# triac.net
KiCad netlist of a schematic drawn in Altium Designer
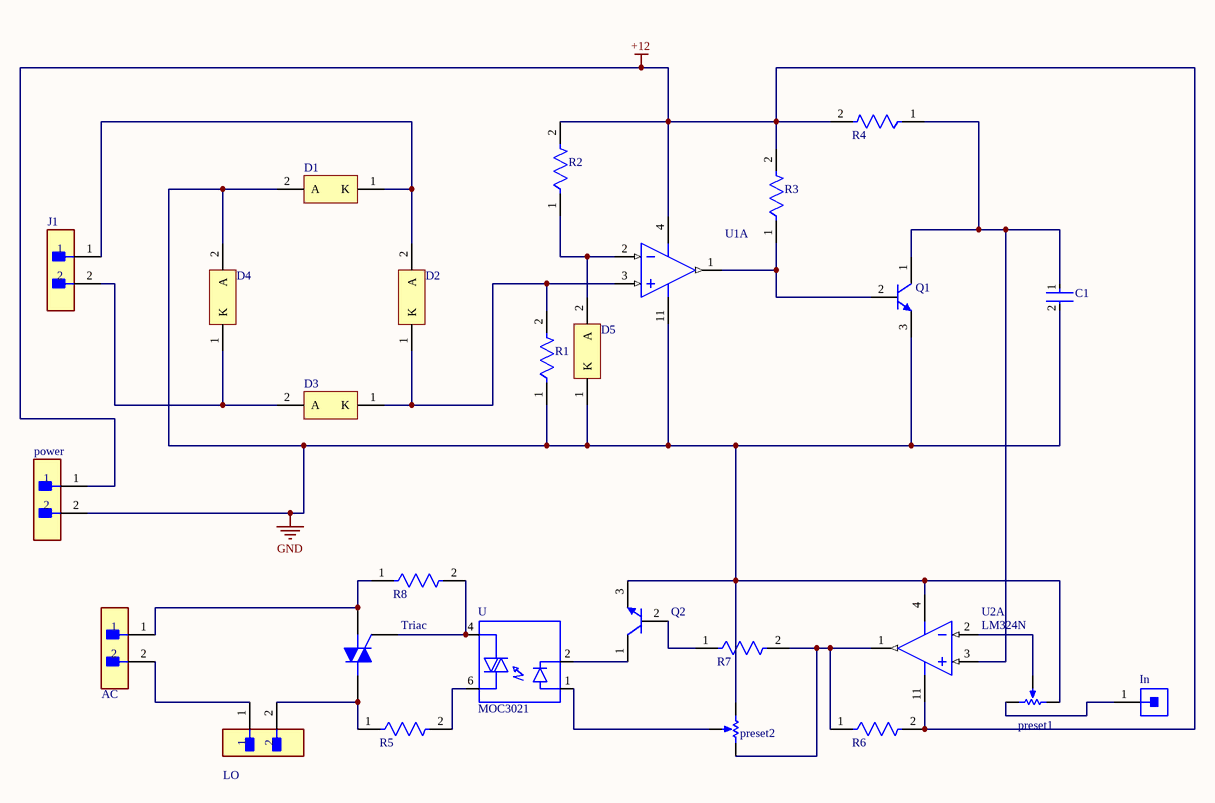
[diagram p0: triac.SchDoc]

(export (version "E")
  (design (tool "Eeschema 10.0.6"))
  (components
    (comp (ref "AC")
      (value "M20-9990246")
      (footprint "FP-M20-9990246-MFG")
      (description "CONN HEADER VERT 2POS 2.54MM")
      (fields
        (field (name "OCTOPART") "https://octopart.com/m20-9990246-harwin-2590635")
        (field (name "MANUFACTURER") "Harwin")
      )
      (libsource (lib "Altium Content Vault") (part "3bc925449376181038e59eaffc5286c"))
    )
    (comp (ref "C1")
      (value "RCE5C1H332J0M1H03A")
      (footprint "FP-RCE0K1-MFG")
      (description "Cap Ceramic 3.3nF 50V C0G ±5% Radial 5mm +125°C Automotive Bulk")
      (fields (field (name "TOLERANCE") "5%"))
      (libsource (lib "Altium Content Vault") (part "b4654b650e69147ec39a6b967a45e02"))
    )
    (comp (ref "D1")
      (value "1N4007G")
      (footprint "ONSC-AXIAL_LEAD-2-59-10_P")
      (description "Standard Recovery Rectifier, 2-Pin Axial_Lead, Pb-Free, Bulk Bag")
      (fields (field (name "MANUFACTURER") "On Semiconductor"))
      (libsource (lib "") (part "ONSC-D-K1A2-2_A_1"))
    )
    (comp (ref "D2")
      (value "1N4007G")
      (footprint "ONSC-AXIAL_LEAD-2-59-10_P")
      (description "Standard Recovery Rectifier, 2-Pin Axial_Lead, Pb-Free, Bulk Bag")
      (fields (field (name "MANUFACTURER") "On Semiconductor"))
      (libsource (lib "Altium Content Vault") (part "ONSC-D-K1A2-2_A"))
    )
    (comp (ref "D3")
      (value "1N4007G")
      (footprint "ONSC-AXIAL_LEAD-2-59-10_P")
      (description "Standard Recovery Rectifier, 2-Pin Axial_Lead, Pb-Free, Bulk Bag")
      (fields (field (name "MANUFACTURER") "On Semiconductor"))
      (libsource (lib "") (part "ONSC-D-K1A2-2_A_1"))
    )
    (comp (ref "D4")
      (value "1N4007G")
      (footprint "ONSC-AXIAL_LEAD-2-59-10_P")
      (description "Standard Recovery Rectifier, 2-Pin Axial_Lead, Pb-Free, Bulk Bag")
      (fields (field (name "MANUFACTURER") "On Semiconductor"))
      (libsource (lib "Altium Content Vault") (part "ONSC-D-K1A2-2_A"))
    )
    (comp (ref "D5")
      (value "1N4007G")
      (footprint "ONSC-AXIAL_LEAD-2-59-10_P")
      (description "Standard Recovery Rectifier, 2-Pin Axial_Lead, Pb-Free, Bulk Bag")
      (fields (field (name "MANUFACTURER") "On Semiconductor"))
      (libsource (lib "Altium Content Vault") (part "ONSC-D-K1A2-2_A"))
    )
    (comp (ref "In")
      (value "61300111121")
      (footprint "61300111121")
      (description "THT Vertical Pin Header WR-PHD, Pitch 2.54 mm, Single Row, 1 pins")
      (fields (field (name "MANUFACTURER") "Wurth Elektronik") (field (name "PUBLISHER") "WurthElektronik"))
      (libsource (lib "Altium Content Vault") (part "WE-CN-1P-M-R1"))
    )
    (comp (ref "J1")
      (value "M20-9990246")
      (footprint "FP-M20-9990246-MFG")
      (description "CONN HEADER VERT 2POS 2.54MM")
      (fields
        (field (name "OCTOPART") "https://octopart.com/m20-9990246-harwin-2590635")
        (field (name "MANUFACTURER") "Harwin")
      )
      (libsource (lib "Altium Content Vault") (part "3bc925449376181038e59eaffc5286c"))
    )
    (comp (ref "LO")
      (value "M20-9990246")
      (footprint "FP-M20-9990246-MFG")
      (description "CONN HEADER VERT 2POS 2.54MM")
      (fields
        (field (name "OCTOPART") "https://octopart.com/m20-9990246-harwin-2590635")
        (field (name "MANUFACTURER") "Harwin")
      )
      (libsource (lib "") (part "3bc925449376181038e59eaffc5286c_1"))
    )
    (comp (ref "power")
      (value "M20-9990246")
      (footprint "FP-M20-9990246-MFG")
      (description "CONN HEADER VERT 2POS 2.54MM")
      (fields
        (field (name "OCTOPART") "https://octopart.com/m20-9990246-harwin-2590635")
        (field (name "MANUFACTURER") "Harwin")
      )
      (libsource (lib "Altium Content Vault") (part "3bc925449376181038e59eaffc5286c"))
    )
    (comp (ref "preset1")
      (value "3362P-1-103LF")
      (footprint "BOUR-3362P")
      (description "Square Trimpot(R) Trimming Potentiometer, 10 KOhm, 300 V, -55 to 125 degC, 3-Pin THD, RoHS, Tube")
      (fields (field (name "TOLERANCE") "1%"))
      (libsource (lib "Altium Content Vault") (part "RES-POT-3"))
    )
    (comp (ref "preset2")
      (value "3362P-1-103LF")
      (footprint "BOUR-3362P")
      (description "Square Trimpot(R) Trimming Potentiometer, 10 KOhm, 300 V, -55 to 125 degC, 3-Pin THD, RoHS, Tube")
      (fields (field (name "TOLERANCE") "1%"))
      (libsource (lib "Altium Content Vault") (part "RES-POT-3"))
    )
    (comp (ref "Q1")
      (value "BC547BG")
      (footprint "ONSC-TO-92-3-29-11")
      (description "Amplifier Transistor, NPN Silicon, 3-Pin TO-92, Pb-Free, Bulk Box")
      (fields (field (name "MANUFACTURER") "On Semiconductor"))
      (libsource (lib "Altium Content Vault") (part "ONSC-NPN-C1B2E3-3"))
    )
    (comp (ref "Q2")
      (value "BC547BG")
      (footprint "ONSC-TO-92-3-29-11")
      (description "Amplifier Transistor, NPN Silicon, 3-Pin TO-92, Pb-Free, Bulk Box")
      (fields (field (name "MANUFACTURER") "On Semiconductor"))
      (libsource (lib "Altium Content Vault") (part "ONSC-NPN-C1B2E3-3"))
    )
    (comp (ref "R1")
      (value "MFR-25FBF52-1K18")
      (footprint "FP-MFR-25-MFG")
      (description "RES 1.18K OHM 1/4W 1% AXIAL")
      (fields (field (name "MANUFACTURER") "Yageo") (field (name "TOLERANCE") "1%"))
      (libsource (lib "Altium Content Vault") (part "1029c3af85768c4190bb7ad29bc67b5"))
    )
    (comp (ref "R2")
      (value "MFR-25FBF52-1K18")
      (footprint "FP-MFR-25-MFG")
      (description "RES 1.18K OHM 1/4W 1% AXIAL")
      (fields (field (name "MANUFACTURER") "Yageo") (field (name "TOLERANCE") "1%"))
      (libsource (lib "Altium Content Vault") (part "1029c3af85768c4190bb7ad29bc67b5"))
    )
    (comp (ref "R3")
      (value "MFR-25FBF52-1K18")
      (footprint "FP-MFR-25-MFG")
      (description "RES 1.18K OHM 1/4W 1% AXIAL")
      (fields (field (name "MANUFACTURER") "Yageo") (field (name "TOLERANCE") "1%"))
      (libsource (lib "Altium Content Vault") (part "1029c3af85768c4190bb7ad29bc67b5"))
    )
    (comp (ref "R4")
      (value "MFR-25FBF52-1K18")
      (footprint "FP-MFR-25-MFG")
      (description "RES 1.18K OHM 1/4W 1% AXIAL")
      (fields (field (name "MANUFACTURER") "Yageo") (field (name "TOLERANCE") "1%"))
      (libsource (lib "Altium Content Vault") (part "1029c3af85768c4190bb7ad29bc67b5"))
    )
    (comp (ref "R5")
      (value "MFR-25FBF52-1K18")
      (footprint "FP-MFR-25-MFG")
      (description "RES 1.18K OHM 1/4W 1% AXIAL")
      (fields (field (name "MANUFACTURER") "Yageo") (field (name "TOLERANCE") "1%"))
      (libsource (lib "Altium Content Vault") (part "1029c3af85768c4190bb7ad29bc67b5"))
    )
    (comp (ref "R6")
      (value "MFR-25FBF52-1K18")
      (footprint "FP-MFR-25-MFG")
      (description "RES 1.18K OHM 1/4W 1% AXIAL")
      (fields (field (name "MANUFACTURER") "Yageo") (field (name "TOLERANCE") "1%"))
      (libsource (lib "Altium Content Vault") (part "1029c3af85768c4190bb7ad29bc67b5"))
    )
    (comp (ref "R7")
      (value "MFR-25FBF52-1K18")
      (footprint "FP-MFR-25-MFG")
      (description "RES 1.18K OHM 1/4W 1% AXIAL")
      (fields (field (name "MANUFACTURER") "Yageo") (field (name "TOLERANCE") "1%"))
      (libsource (lib "Altium Content Vault") (part "1029c3af85768c4190bb7ad29bc67b5"))
    )
    (comp (ref "R8")
      (value "MFR-25FBF52-1K18")
      (footprint "FP-MFR-25-MFG")
      (description "RES 1.18K OHM 1/4W 1% AXIAL")
      (fields (field (name "MANUFACTURER") "Yageo") (field (name "TOLERANCE") "1%"))
      (libsource (lib "Altium Content Vault") (part "1029c3af85768c4190bb7ad29bc67b5"))
    )
    (comp (ref "Triac")
      (value "Triac")
      (footprint "369-03")
      (description "Silicon Bidirectional Triode Thyristor")
      (fields (field (name "PUBLISHER") "Altium Limited"))
      (libsource (lib "Miscellaneous Devices") (part "Triac"))
    )
    (comp (ref "U")
      (value "MOC3021")
      (footprint "DIP762W45P254L889H508Q6")
      (description "Optoisolator Triac Output 5000Vrms 1 Channel 6-DIP")
      (fields (field (name "MF") "Lite-On"))
      (libsource (lib "MOC3021") (part "MOC3021"))
    )
    (comp (ref "U1")
      (value "LM324N")
      (footprint "N0014A")
      (description "Low Power Quad Operational Amplifier, 14-pin MDIP")
      (fields (field (name "MANUFACTURER") "Texas Instruments"))
      (libsource (lib "Altium Content Vault") (part "AMP-OPA-LM124-14"))
    )
    (comp (ref "U2")
      (value "LM324N")
      (footprint "N0014A")
      (description "Low Power Quad Operational Amplifier, 14-pin MDIP")
      (fields (field (name "MANUFACTURER") "Texas Instruments"))
      (libsource (lib "") (part "AMP-OPA-LM124-14_1"))
    )
  )
  (nets
    (net (code "1") (name "+12") (class "Default")
      (node (ref "R2") (pin "2") (pinfunction "2_2") (pintype "passive"))
      (node (ref "R3") (pin "2") (pinfunction "2_2") (pintype "passive"))
      (node (ref "R4") (pin "2") (pinfunction "2_2") (pintype "passive"))
      (node (ref "R6") (pin "2") (pinfunction "2_2") (pintype "passive"))
      (node (ref "U1") (pin "4") (pinfunction "V+_4") (pintype "power_in"))
      (node (ref "U2") (pin "11") (pinfunction "GND_11") (pintype "power_in"))
      (node (ref "power") (pin "1") (pinfunction "1_1") (pintype "passive"))
    )
    (net (code "2") (name "GND") (class "Default")
      (node (ref "C1") (pin "2") (pinfunction "2_2") (pintype "passive"))
      (node (ref "D1") (pin "2") (pinfunction "A_2") (pintype "passive"))
      (node (ref "D4") (pin "2") (pinfunction "A_2") (pintype "passive"))
      (node (ref "D5") (pin "1") (pinfunction "K_1") (pintype "passive"))
      (node (ref "Q1") (pin "3") (pinfunction "E_3") (pintype "passive"))
      (node (ref "Q2") (pin "3") (pinfunction "E_3") (pintype "passive"))
      (node (ref "R1") (pin "1") (pinfunction "1_1") (pintype "passive"))
      (node (ref "U1") (pin "11") (pinfunction "GND_11") (pintype "power_in"))
      (node (ref "U2") (pin "4") (pinfunction "V+_4") (pintype "power_in"))
      (node (ref "power") (pin "2") (pinfunction "2_2") (pintype "passive"))
      (node (ref "preset1") (pin "1") (pinfunction "CCW_1") (pintype "passive"))
      (node (ref "preset2") (pin "1") (pinfunction "CCW_1") (pintype "passive"))
    )
    (net (code "3") (name "Net-(AC-Pad2)") (class "Default")
      (node (ref "AC") (pin "2") (pinfunction "2_2") (pintype "passive"))
      (node (ref "LO") (pin "1") (pinfunction "1_1") (pintype "passive"))
    )
    (net (code "4") (name "Net-(D1-K)") (class "Default")
      (node (ref "D1") (pin "1") (pinfunction "K_1") (pintype "passive"))
      (node (ref "D2") (pin "2") (pinfunction "A_2") (pintype "passive"))
      (node (ref "J1") (pin "1") (pinfunction "1_1") (pintype "passive"))
    )
    (net (code "5") (name "Net-(D2-K)") (class "Default")
      (node (ref "D2") (pin "1") (pinfunction "K_1") (pintype "passive"))
      (node (ref "D3") (pin "1") (pinfunction "K_1") (pintype "passive"))
      (node (ref "R1") (pin "2") (pinfunction "2_2") (pintype "passive"))
      (node (ref "U1") (pin "3") (pinfunction "IN1+_3") (pintype "input"))
    )
    (net (code "6") (name "Net-(D3-A)") (class "Default")
      (node (ref "D3") (pin "2") (pinfunction "A_2") (pintype "passive"))
      (node (ref "D4") (pin "1") (pinfunction "K_1") (pintype "passive"))
      (node (ref "J1") (pin "2") (pinfunction "2_2") (pintype "passive"))
    )
    (net (code "7") (name "Net-(D5-A)") (class "Default")
      (node (ref "D5") (pin "2") (pinfunction "A_2") (pintype "passive"))
      (node (ref "R2") (pin "1") (pinfunction "1_1") (pintype "passive"))
      (node (ref "U1") (pin "2") (pinfunction "IN1-_2") (pintype "input"))
    )
    (net (code "8") (name "Net-(Q1-B)") (class "Default")
      (node (ref "Q1") (pin "2") (pinfunction "B_2") (pintype "passive"))
      (node (ref "R3") (pin "1") (pinfunction "1_1") (pintype "passive"))
      (node (ref "U1") (pin "1") (pinfunction "OUT1_1") (pintype "output"))
    )
    (net (code "9") (name "Net-(Q1-C)") (class "Default")
      (node (ref "C1") (pin "1") (pinfunction "1_1") (pintype "passive"))
      (node (ref "Q1") (pin "1") (pinfunction "C_1") (pintype "passive"))
      (node (ref "R4") (pin "1") (pinfunction "1_1") (pintype "passive"))
      (node (ref "U2") (pin "3") (pinfunction "IN1+_3") (pintype "input"))
    )
    (net (code "10") (name "Net-(Q2-B)") (class "Default")
      (node (ref "Q2") (pin "2") (pinfunction "B_2") (pintype "passive"))
      (node (ref "R7") (pin "1") (pinfunction "1_1") (pintype "passive"))
    )
    (net (code "11") (name "Net-(Q2-C)") (class "Default")
      (node (ref "Q2") (pin "1") (pinfunction "C_1") (pintype "passive"))
      (node (ref "U") (pin "2") (pinfunction "CATODE_2") (pintype "passive"))
    )
    (net (code "12") (name "Net-(Triac-G)") (class "Default")
      (node (ref "R8") (pin "2") (pinfunction "2_2") (pintype "passive"))
      (node (ref "Triac") (pin "3") (pinfunction "G_3") (pintype "passive"))
      (node (ref "U") (pin "4") (pinfunction "MAIN_TERM2_4") (pintype "passive"))
    )
    (net (code "13") (name "Net-(Triac-M1)") (class "Default")
      (node (ref "AC") (pin "1") (pinfunction "1_1") (pintype "passive"))
      (node (ref "R8") (pin "1") (pinfunction "1_1") (pintype "passive"))
      (node (ref "Triac") (pin "1") (pinfunction "M1_1") (pintype "passive"))
    )
    (net (code "14") (name "Net-(Triac-M2)") (class "Default")
      (node (ref "LO") (pin "2") (pinfunction "2_2") (pintype "passive"))
      (node (ref "R5") (pin "1") (pinfunction "1_1") (pintype "passive"))
      (node (ref "Triac") (pin "2") (pinfunction "M2_2") (pintype "passive"))
    )
    (net (code "15") (name "Net-(U-ANODE)") (class "Default")
      (node (ref "U") (pin "1") (pinfunction "ANODE_1") (pintype "passive"))
      (node (ref "preset2") (pin "2") (pinfunction "S_2") (pintype "passive"))
    )
    (net (code "16") (name "Net-(U-MAIN_TERM1)") (class "Default")
      (node (ref "R5") (pin "2") (pinfunction "2_2") (pintype "passive"))
      (node (ref "U") (pin "6") (pinfunction "MAIN_TERM1_6") (pintype "passive"))
    )
    (net (code "17") (name "Net-(U2A-IN1-)") (class "Default")
      (node (ref "U2") (pin "2") (pinfunction "IN1-_2") (pintype "input"))
      (node (ref "preset1") (pin "2") (pinfunction "S_2") (pintype "passive"))
    )
    (net (code "18") (name "Net-(U2A-OUT1)") (class "Default")
      (node (ref "R6") (pin "1") (pinfunction "1_1") (pintype "passive"))
      (node (ref "R7") (pin "2") (pinfunction "2_2") (pintype "passive"))
      (node (ref "U2") (pin "1") (pinfunction "OUT1_1") (pintype "output"))
      (node (ref "preset2") (pin "3") (pinfunction "CW_3") (pintype "passive"))
    )
    (net (code "19") (name "Net-(preset1-CW)") (class "Default")
      (node (ref "In") (pin "1") (pinfunction "1_1") (pintype "passive"))
      (node (ref "preset1") (pin "3") (pinfunction "CW_3") (pintype "passive"))
    )
  )
)
